# LEDboard.net
KiCad netlist of a schematic drawn in Altium Designer
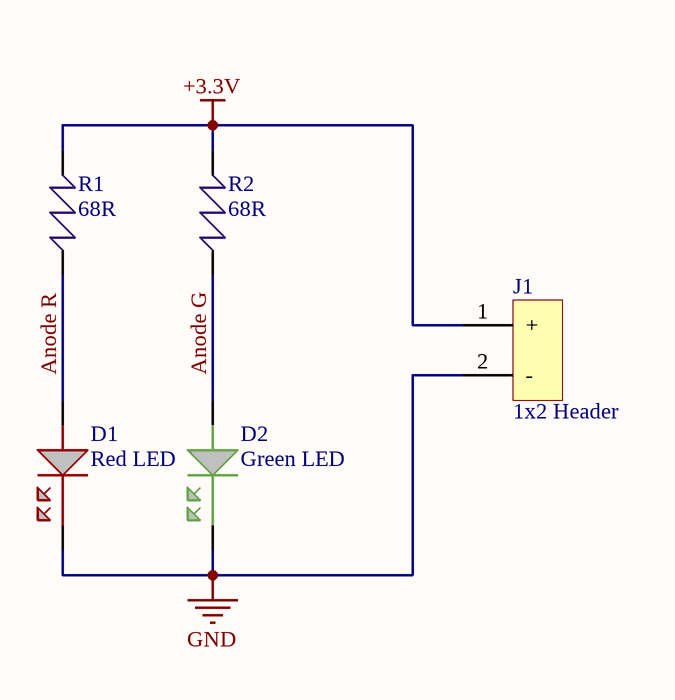
[diagram p0: LEDboard.SchDoc]

(export (version "E")
  (design (tool "Eeschema 10.0.6"))
  (components
    (comp (ref "D1")
      (value "Red LED")
      (footprint "DIODE_RED")
      (description "LED Low-Power Uni-Color Red 630nm 2V 2-Pin Chip 0603(1608Metric) T/R")
      (fields
        (field (name "MANUFACTURER") "Wurth Electronics")
        (field (name "MANUFACTURER PART NUMBER") "150060RS75000")
      )
      (libsource (lib "LEDboard") (part "150060RS75000"))
    )
    (comp (ref "D2")
      (value "Green LED")
      (footprint "Diode_Green")
      (description "WL-SMCD SMT Mono-color Chip LED Diffused")
      (fields
        (field (name "MANUFACTURER") "Wurth Electronics")
        (field (name "MANUFACTURER PART NUMBER") "150060VS55040")
      )
      (libsource (lib "LEDboard") (part "150060VS55040"))
    )
    (comp (ref "J1")
      (value "1x2 Header")
      (footprint "Header_2pin")
      (description "KK 254 Wire-to-Board Header, Vertical, with Friction Lock, 2 Circuits, Gold (Au) Plating")
      (fields (field (name "MANUFACTURER") "Molex") (field (name "MANUFACTURER PART NUMBER") "22-29-2021"))
      (libsource (lib "LEDboard") (part "22-29-2021"))
    )
    (comp (ref "R1")
      (value "68R")
      (footprint "R68")
      (description "SMD Chip Resistor, 68 Ohm, ± 1%, 125 mW, 0805 [2012 Metric], Thick Film, General Purpose")
      (fields
        (field (name "MANUFACTURER") "Vishay")
        (field (name "MANUFACTURER PART NUMBER") "CRCW080568R0FKEAC")
      )
      (libsource (lib "LEDboard") (part "CRCW080568R0FKEAC"))
    )
    (comp (ref "R2")
      (value "68R")
      (footprint "R68")
      (description "SMD Chip Resistor, 68 Ohm, ± 1%, 125 mW, 0805 [2012 Metric], Thick Film, General Purpose")
      (fields
        (field (name "MANUFACTURER") "Vishay")
        (field (name "MANUFACTURER PART NUMBER") "CRCW080568R0FKEAC")
      )
      (libsource (lib "LEDboard") (part "CRCW080568R0FKEAC"))
    )
  )
  (nets
    (net (code "1") (name "+3.3V") (class "Default")
      (node (ref "J1") (pin "1") (pinfunction "+_1") (pintype "passive"))
      (node (ref "R1") (pin "1") (pinfunction "*_1") (pintype "passive"))
      (node (ref "R2") (pin "1") (pinfunction "*_1") (pintype "passive"))
    )
    (net (code "2") (name "/Anode G") (class "Default")
      (node (ref "D2") (pin "2") (pinfunction "*_2") (pintype "passive"))
      (node (ref "R2") (pin "2") (pinfunction "*_2") (pintype "passive"))
    )
    (net (code "3") (name "/Anode R") (class "Default")
      (node (ref "D1") (pin "2") (pinfunction "*_2") (pintype "passive"))
      (node (ref "R1") (pin "2") (pinfunction "*_2") (pintype "passive"))
    )
    (net (code "4") (name "GND") (class "Default")
      (node (ref "D1") (pin "1") (pinfunction "*_1") (pintype "passive"))
      (node (ref "D2") (pin "1") (pinfunction "*_1") (pintype "passive"))
      (node (ref "J1") (pin "2") (pinfunction "-_2") (pintype "passive"))
    )
  )
)
